# BilgeFanDriver.net
KiCad netlist of a schematic drawn in Altium Designer
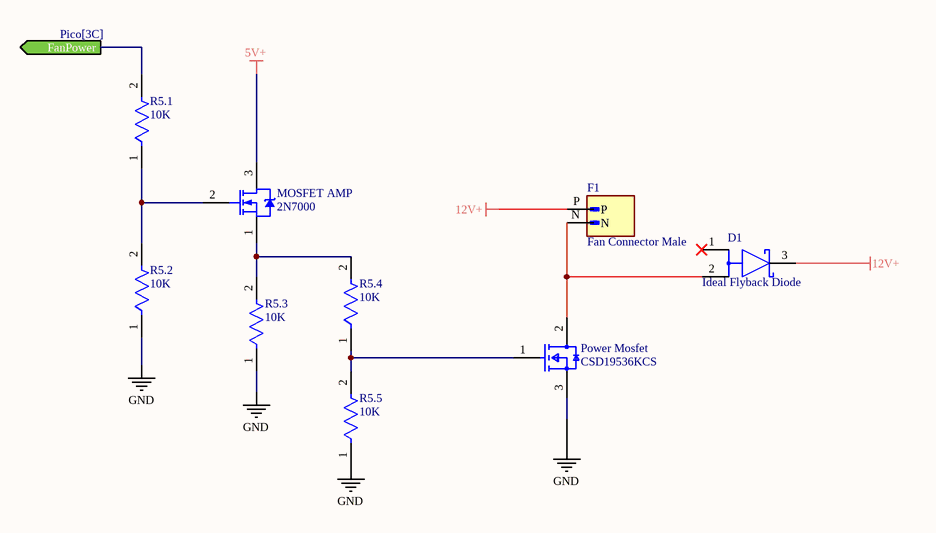
[diagram p0: BilgeFanDriver.SchDoc]

(export (version "E")
  (design (tool "Eeschema 10.0.6"))
  (components
    (comp (ref "D1")
      (value "Ideal Flyback Diode")
      (footprint "FP-340BQ-MFG")
      (description "Rectifier Diode, Schottky, 1 Phase, 1 Element, 5A, 40V V(RRM), Silicon, TO-277")
      (libsource (lib "Yha249 Yha249") (part "e8ae51e072eaf399f4dd16877b8cc48"))
    )
    (comp (ref "F1")
      (value "Fan Connector Male")
      (footprint "AMASS_XT30UPB-M")
      (description "Socket; DC supply; XT30; male; PIN: 2; on PCBs; THT; yellow; 15A; 500V")
      (fields (field (name "MF") "amass") (field (name "MP") "XT30UPB-M"))
      (libsource (lib "XT30UPB-M") (part "XT30UPB-M"))
    )
    (comp (ref "MOSFET AMP")
      (value "2N7000")
      (footprint "ONSC-TO-92-3-29-11")
      (description "Small Signal MOSFET, 200 mA, 60 V, N-Channel, 3-Pin TO-92, Bulk Box")
      (fields (field (name "MANUFACTURER") "On Semiconductor"))
      (libsource (lib "Altium Content Vault") (part "ONSC-NMOS-S1G2D3-3"))
    )
    (comp (ref "Power Mosfet")
      (value "CSD19536KCS")
      (footprint "FP-KCS0003B-MFG")
      (description "MOSFET N-CH 100V TO-220")
      (libsource (lib "Altium Content Vault") (part "139029894f982c57c9000b0e8f69b7b"))
    )
    (comp (ref "R5.1")
      (value "10K")
      (footprint "FP-MFR-12-MFG")
      (description "RES MF 1/6W 1% AXIAL")
      (fields (field (name "TOLERANCE") "1%"))
      (libsource (lib "Altium Content Vault") (part "1029c3af85768c4190bb7ad29bc67b5"))
    )
    (comp (ref "R5.2")
      (value "10K")
      (footprint "FP-MFR-12-MFG")
      (description "RES MF 1/6W 1% AXIAL")
      (fields (field (name "TOLERANCE") "1%"))
      (libsource (lib "Altium Content Vault") (part "1029c3af85768c4190bb7ad29bc67b5"))
    )
    (comp (ref "R5.3")
      (value "10K")
      (footprint "FP-MFR-12-MFG")
      (description "RES MF 1/6W 1% AXIAL")
      (fields (field (name "TOLERANCE") "1%"))
      (libsource (lib "Altium Content Vault") (part "1029c3af85768c4190bb7ad29bc67b5"))
    )
    (comp (ref "R5.4")
      (value "10K")
      (footprint "FP-MFR-12-MFG")
      (description "RES MF 1/6W 1% AXIAL")
      (fields (field (name "TOLERANCE") "1%"))
      (libsource (lib "Altium Content Vault") (part "1029c3af85768c4190bb7ad29bc67b5"))
    )
    (comp (ref "R5.5")
      (value "10K")
      (footprint "FP-MFR-12-MFG")
      (description "RES MF 1/6W 1% AXIAL")
      (fields (field (name "TOLERANCE") "1%"))
      (libsource (lib "Altium Content Vault") (part "1029c3af85768c4190bb7ad29bc67b5"))
    )
  )
  (nets
    (net (code "1") (name "/FanPower") (class "Default")
      (node (ref "R5.1") (pin "2") (pinfunction "2_2") (pintype "passive"))
    )
    (net (code "2") (name "5V+") (class "Default")
      (node (ref "MOSFET AMP") (pin "3") (pinfunction "D_3") (pintype "passive"))
    )
    (net (code "3") (name "12V+") (class "Default")
      (node (ref "D1") (pin "3") (pinfunction "C_3") (pintype "passive"))
      (node (ref "F1") (pin "P") (pinfunction "P_P") (pintype "passive"))
    )
    (net (code "4") (name "GND") (class "Default")
      (node (ref "Power Mosfet") (pin "3") (pinfunction "Source_3") (pintype "passive"))
      (node (ref "R5.2") (pin "1") (pinfunction "1_1") (pintype "passive"))
      (node (ref "R5.3") (pin "1") (pinfunction "1_1") (pintype "passive"))
      (node (ref "R5.5") (pin "1") (pinfunction "1_1") (pintype "passive"))
    )
    (net (code "5") (name "Net-(MOSFET AMP-G)") (class "Default")
      (node (ref "MOSFET AMP") (pin "2") (pinfunction "G_2") (pintype "passive"))
      (node (ref "R5.1") (pin "1") (pinfunction "1_1") (pintype "passive"))
      (node (ref "R5.2") (pin "2") (pinfunction "2_2") (pintype "passive"))
    )
    (net (code "6") (name "Net-(MOSFET AMP-S)") (class "Default")
      (node (ref "MOSFET AMP") (pin "1") (pinfunction "S_1") (pintype "passive"))
      (node (ref "R5.3") (pin "2") (pinfunction "2_2") (pintype "passive"))
      (node (ref "R5.4") (pin "2") (pinfunction "2_2") (pintype "passive"))
    )
    (net (code "7") (name "Net-(Power Mosfet-Drain)") (class "Default")
      (node (ref "D1") (pin "2") (pinfunction "A_2") (pintype "passive"))
      (node (ref "F1") (pin "N") (pinfunction "N_N") (pintype "passive"))
      (node (ref "Power Mosfet") (pin "2") (pinfunction "Drain_2") (pintype "passive"))
    )
    (net (code "8") (name "Net-(Power Mosfet-Gate)") (class "Default")
      (node (ref "Power Mosfet") (pin "1") (pinfunction "Gate_1") (pintype "passive"))
      (node (ref "R5.4") (pin "1") (pinfunction "1_1") (pintype "passive"))
      (node (ref "R5.5") (pin "2") (pinfunction "2_2") (pintype "passive"))
    )
    (net (code "9") (name "unconnected-(D1-A-Pad1)") (class "Default")
      (node (ref "D1") (pin "1") (pinfunction "A_1") (pintype "passive+no_connect"))
    )
  )
)
